# 3_-_USB.net
KiCad netlist of a schematic drawn in Altium Designer
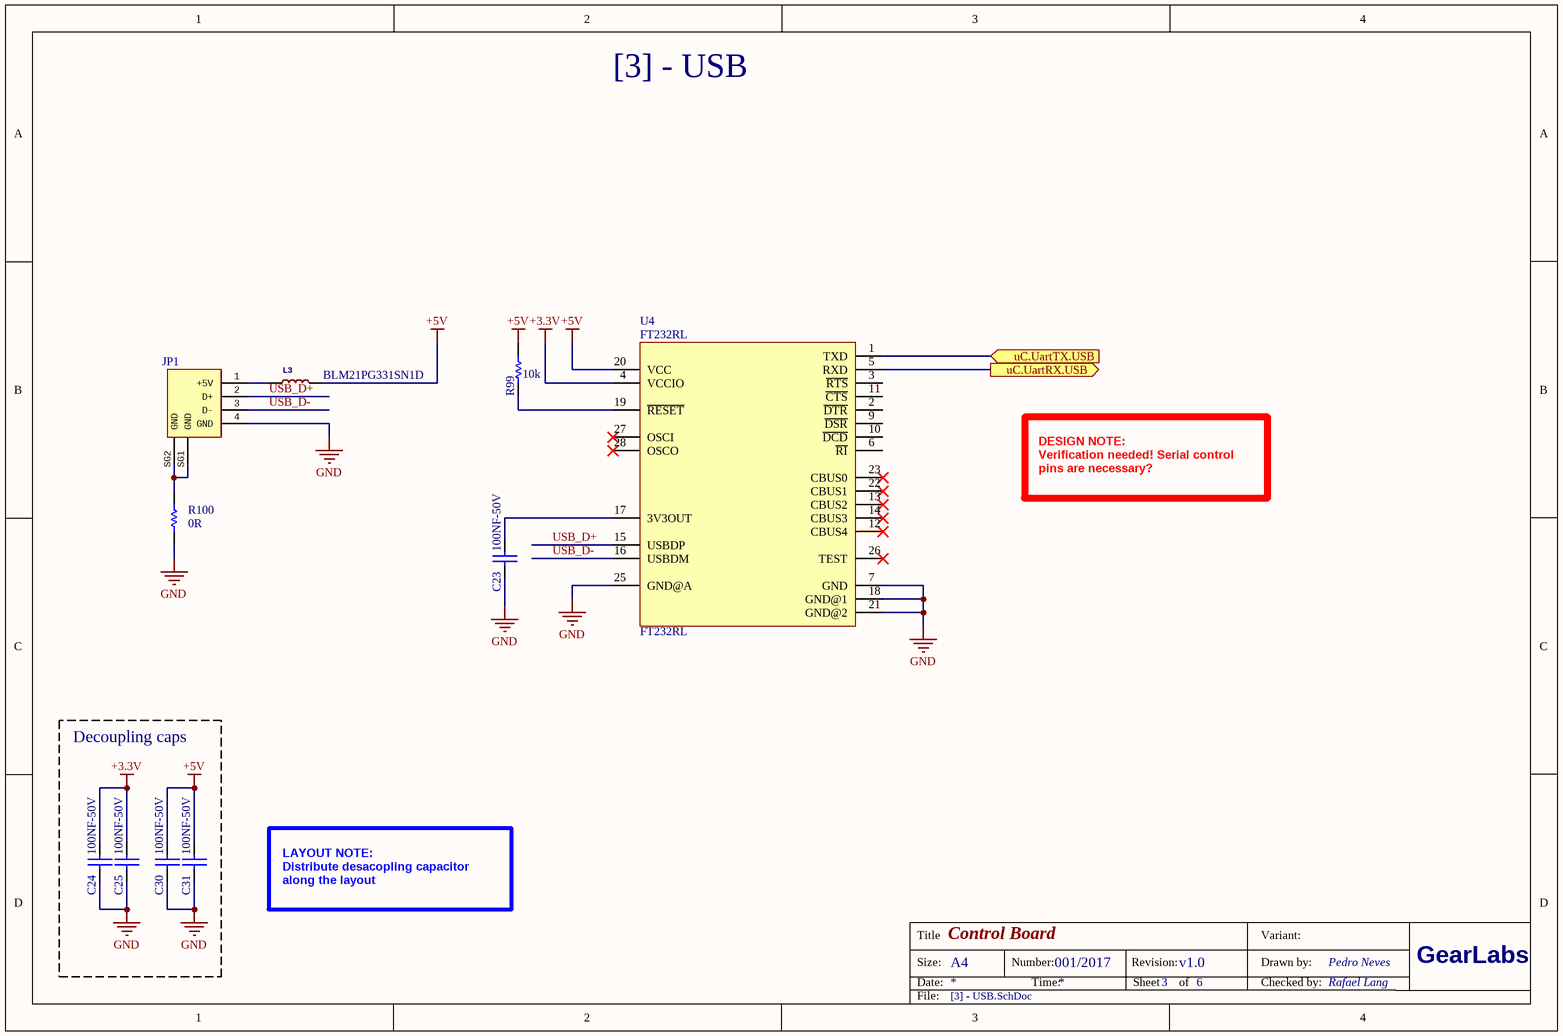
[diagram p0: [3] - USB.SchDoc]

(export (version "E")
  (design (tool "Eeschema 10.0.6"))
  (components
    (comp (ref "C23")
      (value "100NF-50V")
      (footprint "C0603")
      (fields (field (name "MPN") "CC0603KRX7R9BB104") (field (name "Comment") "302010138"))
      (libsource (lib "Seeed-Capacitor") (part "CERAMIC-100NF-50V-10%-X7R(0603)"))
    )
    (comp (ref "C24")
      (value "100NF-50V")
      (footprint "C0603")
      (fields (field (name "MPN") "CC0603KRX7R9BB104") (field (name "Comment") "302010138"))
      (libsource (lib "Seeed-Capacitor") (part "CERAMIC-100NF-50V-10%-X7R(0603)"))
    )
    (comp (ref "C25")
      (value "100NF-50V")
      (footprint "C0603")
      (fields (field (name "MPN") "CC0603KRX7R9BB104") (field (name "Comment") "302010138"))
      (libsource (lib "Seeed-Capacitor") (part "CERAMIC-100NF-50V-10%-X7R(0603)"))
    )
    (comp (ref "C30")
      (value "100NF-50V")
      (footprint "C0603")
      (fields (field (name "MPN") "CC0603KRX7R9BB104") (field (name "Comment") "302010138"))
      (libsource (lib "Seeed-Capacitor") (part "CERAMIC-100NF-50V-10%-X7R(0603)"))
    )
    (comp (ref "C31")
      (value "100NF-50V")
      (footprint "C0603")
      (fields (field (name "MPN") "CC0603KRX7R9BB104") (field (name "Comment") "302010138"))
      (libsource (lib "Seeed-Capacitor") (part "CERAMIC-100NF-50V-10%-X7R(0603)"))
    )
    (comp (ref "JP1")
      (value "320010007")
      (footprint "USB4+2P-2.0-90D")
      (libsource (lib "Seeed-Connector") (part "DIP-USB-A-TYPE-FMAL(4+2P-2.0-90D)"))
    )
    (comp (ref "L3")
      (value "303030006")
      (footprint "L0805")
      (fields (field (name "MPN") "BLM21PG331SN1D"))
      (libsource (lib "Seeed-Inductor") (part "SMD-FERRITE-BEAD-330R-1500MA(0805)'0805'"))
    )
    (comp (ref "R99")
      (value "10k")
      (footprint "R0603")
      (fields (field (name "MPN") "RC0603JR-0710KL") (field (name "Comment") "301010293"))
      (libsource (lib "Seeed-Resistor") (part "SMD-RES-10K-5%-1/10W(0603)"))
    )
    (comp (ref "R100")
      (value "0R")
      (footprint "R0603")
      (fields (field (name "MPN") "RC0603JR-070RL") (field (name "Comment") "301010292"))
      (libsource (lib "Seeed-Resistor") (part "SMD-RES-0R-5%-1/10W(0603)"))
    )
    (comp (ref "U4")
      (value "FT232RL")
      (footprint "SSOP28-0.65-10.2X5.2MM")
      (fields (field (name "MPN") "FT232RL"))
      (libsource (lib "Seeed-IC") (part "INTERFACE-FT232RL(SSOP28)"))
    )
  )
  (nets
    (net (code "1") (name "+3.3V") (class "Default")
      (node (ref "C24") (pin "1") (pinfunction "1_1") (pintype "passive"))
      (node (ref "C25") (pin "1") (pinfunction "1_1") (pintype "passive"))
      (node (ref "U4") (pin "4") (pinfunction "VCCIO_4") (pintype "passive"))
    )
    (net (code "2") (name "+5V") (class "Default")
      (node (ref "C30") (pin "1") (pinfunction "1_1") (pintype "passive"))
      (node (ref "C31") (pin "1") (pinfunction "1_1") (pintype "passive"))
      (node (ref "L3") (pin "2") (pinfunction "2_2") (pintype "passive"))
      (node (ref "R99") (pin "2") (pinfunction "2_2") (pintype "passive"))
      (node (ref "U4") (pin "20") (pinfunction "VCC_20") (pintype "passive"))
    )
    (net (code "3") (name "/USB_D+") (class "Default")
      (node (ref "JP1") (pin "2") (pinfunction "D+_2") (pintype "passive"))
      (node (ref "U4") (pin "15") (pinfunction "USBDP_15") (pintype "passive"))
    )
    (net (code "4") (name "/USB_D-") (class "Default")
      (node (ref "JP1") (pin "3") (pinfunction "D-_3") (pintype "passive"))
      (node (ref "U4") (pin "16") (pinfunction "USBDM_16") (pintype "passive"))
    )
    (net (code "5") (name "/uC.UartRX.USB") (class "Default")
      (node (ref "U4") (pin "5") (pinfunction "RXD_5") (pintype "passive"))
    )
    (net (code "6") (name "/uC.UartTX.USB") (class "Default")
      (node (ref "U4") (pin "1") (pinfunction "TXD_1") (pintype "passive"))
    )
    (net (code "7") (name "GND") (class "Default")
      (node (ref "C23") (pin "2") (pinfunction "2_2") (pintype "passive"))
      (node (ref "C24") (pin "2") (pinfunction "2_2") (pintype "passive"))
      (node (ref "C25") (pin "2") (pinfunction "2_2") (pintype "passive"))
      (node (ref "C30") (pin "2") (pinfunction "2_2") (pintype "passive"))
      (node (ref "C31") (pin "2") (pinfunction "2_2") (pintype "passive"))
      (node (ref "JP1") (pin "4") (pinfunction "GND_4") (pintype "passive"))
      (node (ref "R100") (pin "1") (pinfunction "1_1") (pintype "passive"))
      (node (ref "U4") (pin "18") (pinfunction "GND@1_18") (pintype "passive"))
      (node (ref "U4") (pin "21") (pinfunction "GND@2_21") (pintype "passive"))
      (node (ref "U4") (pin "25") (pinfunction "GND@A_25") (pintype "passive"))
      (node (ref "U4") (pin "7") (pinfunction "GND_7") (pintype "passive"))
    )
    (net (code "8") (name "Net-(JP1-+5V)") (class "Default")
      (node (ref "JP1") (pin "1") (pinfunction "+5V_1") (pintype "passive"))
      (node (ref "L3") (pin "1") (pinfunction "1_1") (pintype "passive"))
    )
    (net (code "9") (name "Net-(JP1-GND-PadSG1)") (class "Default")
      (node (ref "JP1") (pin "SG1") (pinfunction "GND_SG1") (pintype "passive"))
      (node (ref "JP1") (pin "SG2") (pinfunction "GND_SG2") (pintype "passive"))
      (node (ref "R100") (pin "2") (pinfunction "2_2") (pintype "passive"))
    )
    (net (code "10") (name "Net-(U4-3V3OUT)") (class "Default")
      (node (ref "C23") (pin "1") (pinfunction "1_1") (pintype "passive"))
      (node (ref "U4") (pin "17") (pinfunction "3V3OUT_17") (pintype "passive"))
    )
    (net (code "11") (name "Net-(U4-RESET)") (class "Default")
      (node (ref "R99") (pin "1") (pinfunction "1_1") (pintype "passive"))
      (node (ref "U4") (pin "19") (pinfunction "RESET_19") (pintype "passive"))
    )
    (net (code "12") (name "unconnected-(U4-CBUS0-Pad23)") (class "Default")
      (node (ref "U4") (pin "23") (pinfunction "CBUS0_23") (pintype "passive+no_connect"))
    )
    (net (code "13") (name "unconnected-(U4-CBUS1-Pad22)") (class "Default")
      (node (ref "U4") (pin "22") (pinfunction "CBUS1_22") (pintype "passive+no_connect"))
    )
    (net (code "14") (name "unconnected-(U4-CBUS2-Pad13)") (class "Default")
      (node (ref "U4") (pin "13") (pinfunction "CBUS2_13") (pintype "passive+no_connect"))
    )
    (net (code "15") (name "unconnected-(U4-CBUS3-Pad14)") (class "Default")
      (node (ref "U4") (pin "14") (pinfunction "CBUS3_14") (pintype "passive+no_connect"))
    )
    (net (code "16") (name "unconnected-(U4-CBUS4-Pad12)") (class "Default")
      (node (ref "U4") (pin "12") (pinfunction "CBUS4_12") (pintype "passive+no_connect"))
    )
    (net (code "17") (name "unconnected-(U4-CTS-Pad11)") (class "Default")
      (node (ref "U4") (pin "11") (pinfunction "CTS_11") (pintype "passive"))
    )
    (net (code "18") (name "unconnected-(U4-DCD-Pad10)") (class "Default")
      (node (ref "U4") (pin "10") (pinfunction "DCD_10") (pintype "passive"))
    )
    (net (code "19") (name "unconnected-(U4-DSR-Pad9)") (class "Default")
      (node (ref "U4") (pin "9") (pinfunction "DSR_9") (pintype "passive"))
    )
    (net (code "20") (name "unconnected-(U4-DTR-Pad2)") (class "Default")
      (node (ref "U4") (pin "2") (pinfunction "DTR_2") (pintype "passive"))
    )
    (net (code "21") (name "unconnected-(U4-OSCI-Pad27)") (class "Default")
      (node (ref "U4") (pin "27") (pinfunction "OSCI_27") (pintype "passive+no_connect"))
    )
    (net (code "22") (name "unconnected-(U4-OSCO-Pad28)") (class "Default")
      (node (ref "U4") (pin "28") (pinfunction "OSCO_28") (pintype "passive+no_connect"))
    )
    (net (code "23") (name "unconnected-(U4-RI-Pad6)") (class "Default")
      (node (ref "U4") (pin "6") (pinfunction "RI_6") (pintype "passive"))
    )
    (net (code "24") (name "unconnected-(U4-RTS-Pad3)") (class "Default")
      (node (ref "U4") (pin "3") (pinfunction "RTS_3") (pintype "passive"))
    )
    (net (code "25") (name "unconnected-(U4-TEST-Pad26)") (class "Default")
      (node (ref "U4") (pin "26") (pinfunction "TEST_26") (pintype "passive+no_connect"))
    )
  )
)
